# POWERMANAGE2.net
KiCad netlist of a schematic drawn in Altium Designer
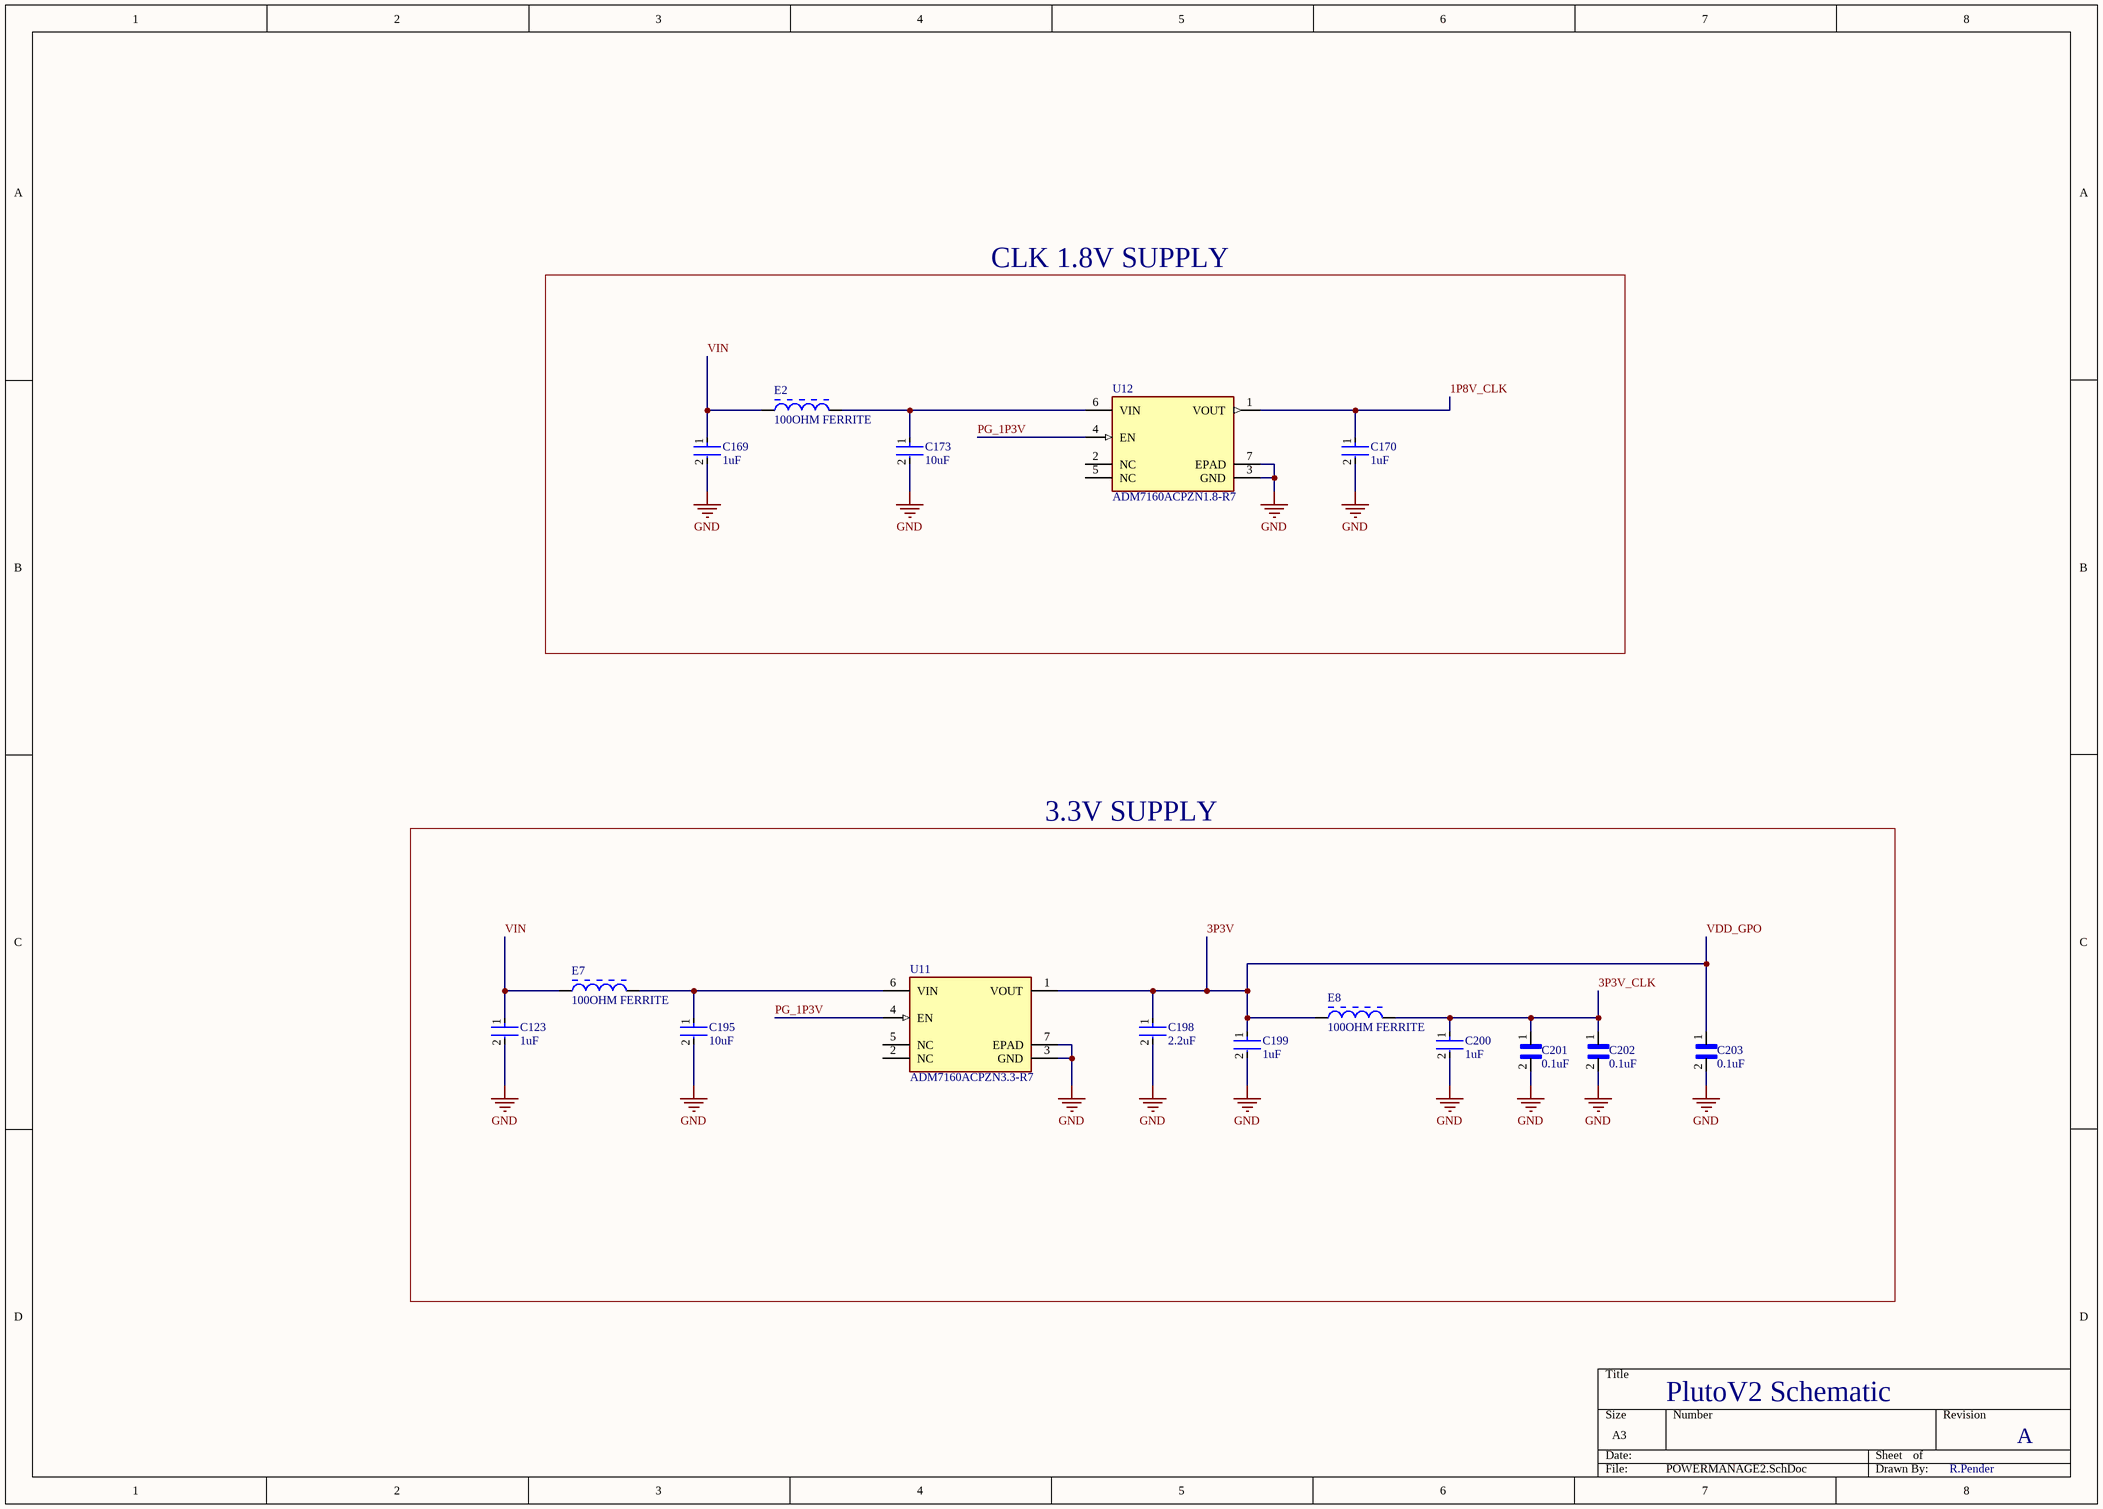
[diagram p0: POWERMANAGE2.SchDoc]

(export (version "E")
  (design (tool "Eeschema 10.0.6"))
  (components
    (comp (ref "C123")
      (value "1uF")
      (footprint "FP-0402-L_1_0_0_05-W_0_5-IPC_A")
      (description "None")
      (fields (field (name "TOLERANCE") "10%"))
      (libsource (lib "Altium Content Vault") (part "b4654b650e69147ec39a6b967a45e02"))
    )
    (comp (ref "C169")
      (value "1uF")
      (footprint "FP-0402-L_1_0_0_05-W_0_5-IPC_A")
      (description "None")
      (fields (field (name "TOLERANCE") "10%"))
      (libsource (lib "Altium Content Vault") (part "b4654b650e69147ec39a6b967a45e02"))
    )
    (comp (ref "C170")
      (value "1uF")
      (footprint "FP-0402-L_1_0_0_05-W_0_5-IPC_B")
      (description "None")
      (fields (field (name "TOLERANCE") "10%"))
      (libsource (lib "Altium Content Vault") (part "b4654b650e69147ec39a6b967a45e02"))
    )
    (comp (ref "C173")
      (value "10uF")
      (footprint "FP-GRM188-0_15-MFG")
      (description "Chip Multilayer Ceramic Capacitors for General Purpose, 0603, 10uF, X5R, 15%, 20%, 10V")
      (fields (field (name "TOLERANCE") "20%"))
      (libsource (lib "Altium Content Vault") (part "02cd4be3c70576c341d710602a673aa"))
    )
    (comp (ref "C195")
      (value "10uF")
      (footprint "FP-GRM188-0_15-MFG")
      (description "Chip Multilayer Ceramic Capacitors for General Purpose, 0603, 10uF, X5R, 15%, 20%, 10V")
      (fields (field (name "TOLERANCE") "20%"))
      (libsource (lib "Altium Content Vault") (part "02cd4be3c70576c341d710602a673aa"))
    )
    (comp (ref "C198")
      (value "2.2uF")
      (footprint "FP-GRM188-0_2-MFG")
      (description "Chip Multilayer Ceramic Capacitors for General Purpose, 0603, 2.2uF, X5R, 15%, 10%, 50V")
      (fields (field (name "TOLERANCE") "10%"))
      (libsource (lib "Altium Content Vault") (part "11868f565c42a9108669ba33697ecf6"))
    )
    (comp (ref "C199")
      (value "1uF")
      (footprint "FP-0402-L_1_0_0_05-W_0_5-IPC_A")
      (description "None")
      (fields (field (name "TOLERANCE") "10%"))
      (libsource (lib "Altium Content Vault") (part "b4654b650e69147ec39a6b967a45e02"))
    )
    (comp (ref "C200")
      (value "1uF")
      (footprint "FP-0402-L_1_0_0_05-W_0_5-IPC_A")
      (description "None")
      (fields (field (name "TOLERANCE") "10%"))
      (libsource (lib "Altium Content Vault") (part "b4654b650e69147ec39a6b967a45e02"))
    )
    (comp (ref "C201")
      (value "0.1uF")
      (footprint "CAPC0603X33N")
      (description "CAP 0.1UF 16VDC X5R 20% SMD 0201 PAPER TAPE")
      (fields (field (name "MP") "GRM033R61C104ME84D"))
      (libsource (lib "GRM033R61C104ME84D") (part "GRM033R61C104ME84D"))
    )
    (comp (ref "C202")
      (value "0.1uF")
      (footprint "CAPC0603X33N")
      (description "CAP 0.1UF 16VDC X5R 20% SMD 0201 PAPER TAPE")
      (fields (field (name "MP") "GRM033R61C104ME84D"))
      (libsource (lib "GRM033R61C104ME84D") (part "GRM033R61C104ME84D"))
    )
    (comp (ref "C203")
      (value "0.1uF")
      (footprint "CAPC0603X33N")
      (description "CAP 0.1UF 16VDC X5R 20% SMD 0201 PAPER TAPE")
      (fields (field (name "MP") "GRM033R61C104ME84D"))
      (libsource (lib "GRM033R61C104ME84D") (part "GRM033R61C104ME84D"))
    )
    (comp (ref "E2")
      (value "100OHM FERRITE")
      (footprint "TDK-MPZ2012S101A-2_V")
      (fields (field (name "TOLERANCE") "25%") (field (name "MANUFACTURER") "TDK"))
      (libsource (lib "Altium Content Vault") (part "BEAD-2"))
    )
    (comp (ref "E7")
      (value "100OHM FERRITE")
      (footprint "TDK-MPZ2012S101A-2_V")
      (fields (field (name "TOLERANCE") "25%") (field (name "MANUFACTURER") "TDK"))
      (libsource (lib "Altium Content Vault") (part "BEAD-2"))
    )
    (comp (ref "E8")
      (value "100OHM FERRITE")
      (footprint "TDK-MPZ2012S101A-2_V")
      (fields (field (name "TOLERANCE") "25%") (field (name "MANUFACTURER") "TDK"))
      (libsource (lib "Altium Content Vault") (part "BEAD-2"))
    )
    (comp (ref "U11")
      (value "ADM7160ACPZN3.3-R7")
      (footprint "FP-CP-6-3-IPC_A")
      (description "IC REG LINEAR 3.3V 200MA 6LFCSP")
      (libsource (lib "Altium Content Vault") (part "1bcd84081306a58d9bf24361e4fa6b1"))
    )
    (comp (ref "U12")
      (value "ADM7160ACPZN1.8-R7")
      (footprint "FP-CP-6-3-IPC_C")
      (description "IC REG LINEAR 1.8V 200MA 6LFCSP")
      (libsource (lib "Altium Content Vault") (part "4c8513698d558cca4e2e33da6060110"))
    )
  )
  (nets
    (net (code "1") (name "/1P8V_CLK") (class "Default")
      (node (ref "C170") (pin "1") (pinfunction "1_1") (pintype "passive"))
      (node (ref "U12") (pin "1") (pinfunction "VOUT_1") (pintype "output"))
    )
    (net (code "2") (name "/3P3V") (class "Default")
      (node (ref "C198") (pin "1") (pinfunction "1_1") (pintype "passive"))
      (node (ref "C199") (pin "1") (pinfunction "1_1") (pintype "passive"))
      (node (ref "C203") (pin "1") (pinfunction "1_1") (pintype "passive"))
      (node (ref "E8") (pin "1") (pinfunction "1_1") (pintype "passive"))
      (node (ref "U11") (pin "1") (pinfunction "VOUT_1") (pintype "power_in"))
    )
    (net (code "3") (name "/3P3V_CLK") (class "Default")
      (node (ref "C200") (pin "1") (pinfunction "1_1") (pintype "passive"))
      (node (ref "C201") (pin "1") (pinfunction "1_1") (pintype "passive"))
      (node (ref "C202") (pin "1") (pinfunction "1_1") (pintype "passive"))
      (node (ref "E8") (pin "2") (pinfunction "2_2") (pintype "passive"))
    )
    (net (code "4") (name "/PG_1P3V") (class "Default")
      (node (ref "U11") (pin "4") (pinfunction "EN_4") (pintype "input"))
      (node (ref "U12") (pin "4") (pinfunction "EN_4") (pintype "input"))
    )
    (net (code "5") (name "/VIN") (class "Default")
      (node (ref "C123") (pin "1") (pinfunction "1_1") (pintype "passive"))
      (node (ref "C169") (pin "1") (pinfunction "1_1") (pintype "passive"))
      (node (ref "E2") (pin "1") (pinfunction "1_1") (pintype "passive"))
      (node (ref "E7") (pin "1") (pinfunction "1_1") (pintype "passive"))
    )
    (net (code "6") (name "GND") (class "Default")
      (node (ref "C123") (pin "2") (pinfunction "2_2") (pintype "passive"))
      (node (ref "C169") (pin "2") (pinfunction "2_2") (pintype "passive"))
      (node (ref "C170") (pin "2") (pinfunction "2_2") (pintype "passive"))
      (node (ref "C173") (pin "2") (pinfunction "2_2") (pintype "passive"))
      (node (ref "C195") (pin "2") (pinfunction "2_2") (pintype "passive"))
      (node (ref "C198") (pin "2") (pinfunction "2_2") (pintype "passive"))
      (node (ref "C199") (pin "2") (pinfunction "2_2") (pintype "passive"))
      (node (ref "C200") (pin "2") (pinfunction "2_2") (pintype "passive"))
      (node (ref "C201") (pin "2") (pinfunction "2_2") (pintype "passive"))
      (node (ref "C202") (pin "2") (pinfunction "2_2") (pintype "passive"))
      (node (ref "C203") (pin "2") (pinfunction "2_2") (pintype "passive"))
      (node (ref "U11") (pin "3") (pinfunction "GND_3") (pintype "power_in"))
      (node (ref "U11") (pin "7") (pinfunction "EPAD_7") (pintype "power_in"))
      (node (ref "U12") (pin "3") (pinfunction "GND_3") (pintype "power_in"))
      (node (ref "U12") (pin "7") (pinfunction "EPAD_7") (pintype "passive"))
    )
    (net (code "7") (name "Net-(U11-VIN)") (class "Default")
      (node (ref "C195") (pin "1") (pinfunction "1_1") (pintype "passive"))
      (node (ref "E7") (pin "2") (pinfunction "2_2") (pintype "passive"))
      (node (ref "U11") (pin "6") (pinfunction "VIN_6") (pintype "power_in"))
    )
    (net (code "8") (name "Net-(U12-VIN)") (class "Default")
      (node (ref "C173") (pin "1") (pinfunction "1_1") (pintype "passive"))
      (node (ref "E2") (pin "2") (pinfunction "2_2") (pintype "passive"))
      (node (ref "U12") (pin "6") (pinfunction "VIN_6") (pintype "power_in"))
    )
    (net (code "9") (name "unconnected-(U11-NC-Pad2)") (class "Default")
      (node (ref "U11") (pin "2") (pinfunction "NC_2") (pintype "passive"))
    )
    (net (code "10") (name "unconnected-(U11-NC-Pad5)") (class "Default")
      (node (ref "U11") (pin "5") (pinfunction "NC_5") (pintype "passive"))
    )
    (net (code "11") (name "unconnected-(U12-NC-Pad2)") (class "Default")
      (node (ref "U12") (pin "2") (pinfunction "NC_2") (pintype "passive"))
    )
    (net (code "12") (name "unconnected-(U12-NC-Pad5)") (class "Default")
      (node (ref "U12") (pin "5") (pinfunction "NC_5") (pintype "passive"))
    )
  )
)
